# PogoMiniSch.net
KiCad netlist of a schematic drawn in Altium Designer
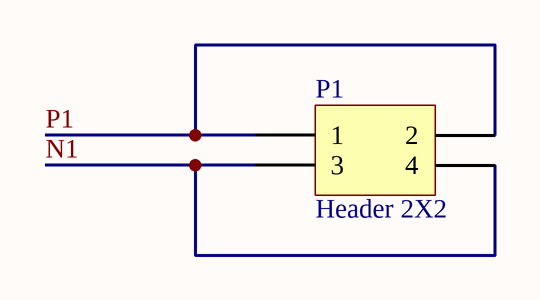
[diagram p0: PogoMiniSch.SchDoc]

(export (version "E")
  (design (tool "Eeschema 10.0.6"))
  (components
    (comp (ref "P1")
      (value "Header 2X2")
      (footprint "HDR2X2")
      (description "Header, 2-Pin, Dual row")
      (fields (field (name "PUBLISHER") "Altium Limited"))
      (libsource (lib "Miscellaneous Connectors") (part "Header 2X2"))
    )
  )
  (nets
    (net (code "1") (name "/N1") (class "Default")
      (node (ref "P1") (pin "3") (pinfunction "3_3") (pintype "passive"))
      (node (ref "P1") (pin "4") (pinfunction "4_4") (pintype "passive"))
    )
    (net (code "2") (name "/P1") (class "Default")
      (node (ref "P1") (pin "1") (pinfunction "1_1") (pintype "passive"))
      (node (ref "P1") (pin "2") (pinfunction "2_2") (pintype "passive"))
    )
  )
)
